# GD_Tcontroller_485.net
KiCad netlist of a schematic drawn in Altium Designer
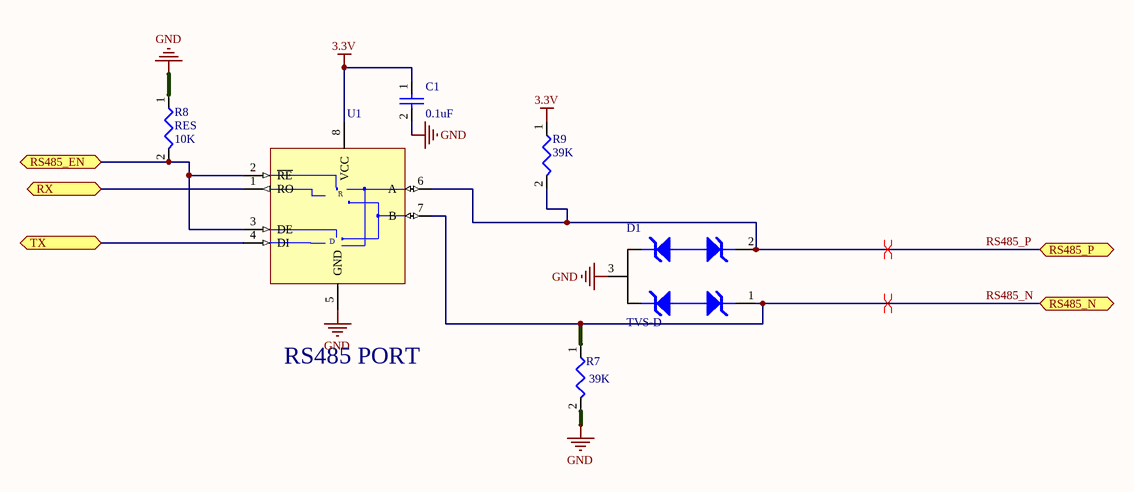
[diagram p0: GD_Tcontroller_485.SchDoc]

(export (version "E")
  (design (tool "Eeschema 10.0.6"))
  (components
    (comp (ref "C1")
      (value "0.1uF")
      (footprint "C0805")
      (description "CAP SMD CR X7R 50V 10% 0.1uF 0805 ROHS")
      (fields (field (name "MANUFACTURER") "YAGEO") (field (name "Comment") "CAP"))
      (libsource (lib "enlogic") (part "CAP"))
    )
    (comp (ref "D1")
      (value "TVS-D")
      (footprint "SOT23-123")
      (description "DIODE TVS 7V 12V 17A 400W SOT-23 SMD ROHS")
      (fields (field (name "MANUFACTURER") "BOURNS"))
      (libsource (lib "enlogic") (part "TVS-D"))
    )
    (comp (ref "R7")
      (value "39K")
      (footprint "R0805")
      (description "RES THICK_FILM SMD 39K 5% 1/8W ROHS 0805")
      (fields (field (name "MANUFACTURER") "YAGEO") (field (name "Comment") "RES"))
      (libsource (lib "enlogic") (part "RES"))
    )
    (comp (ref "R8")
      (value "RES")
      (footprint "R0805")
      (description "RES THICK_FILM SMD 10K ohm 5% 1/10W ROHS 0603")
      (fields (field (name "MANUFACTURER") "YAGEO") (field (name "ALTIUM_VALUE") "10K"))
      (libsource (lib "Enlogic") (part "RES"))
    )
    (comp (ref "R9")
      (value "39K")
      (footprint "R0805")
      (description "RES THICK_FILM SMD 39K 5% 1/8W ROHS 0805")
      (fields (field (name "MANUFACTURER") "YAGEO") (field (name "Comment") "RES"))
      (libsource (lib "enlogic") (part "RES"))
    )
    (comp (ref "U1")
      (value "SN65HVD08D")
      (footprint "SOIC8")
      (description "IC 5V,RS-485,10Mbps,16KV,TRANSCEIVERS,SOIC-8,ROHS")
      (fields (field (name "MANUFACTURER") "Texas Instruments"))
      (libsource (lib "enlogic") (part "SN65HVD11D"))
    )
  )
  (nets
    (net (code "1") (name "/RS485_EN") (class "Default")
      (node (ref "R8") (pin "2") (pinfunction "2_2") (pintype "passive"))
      (node (ref "U1") (pin "2") (pinfunction "~{RE}_2") (pintype "input"))
      (node (ref "U1") (pin "3") (pinfunction "DE_3") (pintype "input"))
    )
    (net (code "2") (name "/RS485_N") (class "Default")
      (node (ref "D1") (pin "1") (pinfunction "1_1") (pintype "passive"))
      (node (ref "R7") (pin "1") (pinfunction "1_1") (pintype "passive"))
      (node (ref "U1") (pin "7") (pinfunction "B_7") (pintype "bidirectional"))
    )
    (net (code "3") (name "/RS485_P") (class "Default")
      (node (ref "D1") (pin "2") (pinfunction "2_2") (pintype "passive"))
      (node (ref "R9") (pin "2") (pinfunction "2_2") (pintype "passive"))
      (node (ref "U1") (pin "6") (pinfunction "A_6") (pintype "bidirectional"))
    )
    (net (code "4") (name "/RX") (class "Default")
      (node (ref "U1") (pin "1") (pinfunction "RO_1") (pintype "output"))
    )
    (net (code "5") (name "/TX") (class "Default")
      (node (ref "U1") (pin "4") (pinfunction "DI_4") (pintype "input"))
    )
    (net (code "6") (name "3.3V") (class "Default")
      (node (ref "C1") (pin "1") (pinfunction "1_1") (pintype "passive"))
      (node (ref "R9") (pin "1") (pinfunction "1_1") (pintype "passive"))
      (node (ref "U1") (pin "8") (pinfunction "VCC_8") (pintype "power_in"))
    )
    (net (code "7") (name "GND") (class "Default")
      (node (ref "C1") (pin "2") (pinfunction "2_2") (pintype "passive"))
      (node (ref "D1") (pin "3") (pinfunction "3_3") (pintype "passive"))
      (node (ref "R7") (pin "2") (pinfunction "2_2") (pintype "passive"))
      (node (ref "R8") (pin "1") (pinfunction "1_1") (pintype "passive"))
      (node (ref "U1") (pin "5") (pinfunction "GND_5") (pintype "power_in"))
    )
  )
)
